# Power.net
KiCad netlist of a schematic drawn in Altium Designer
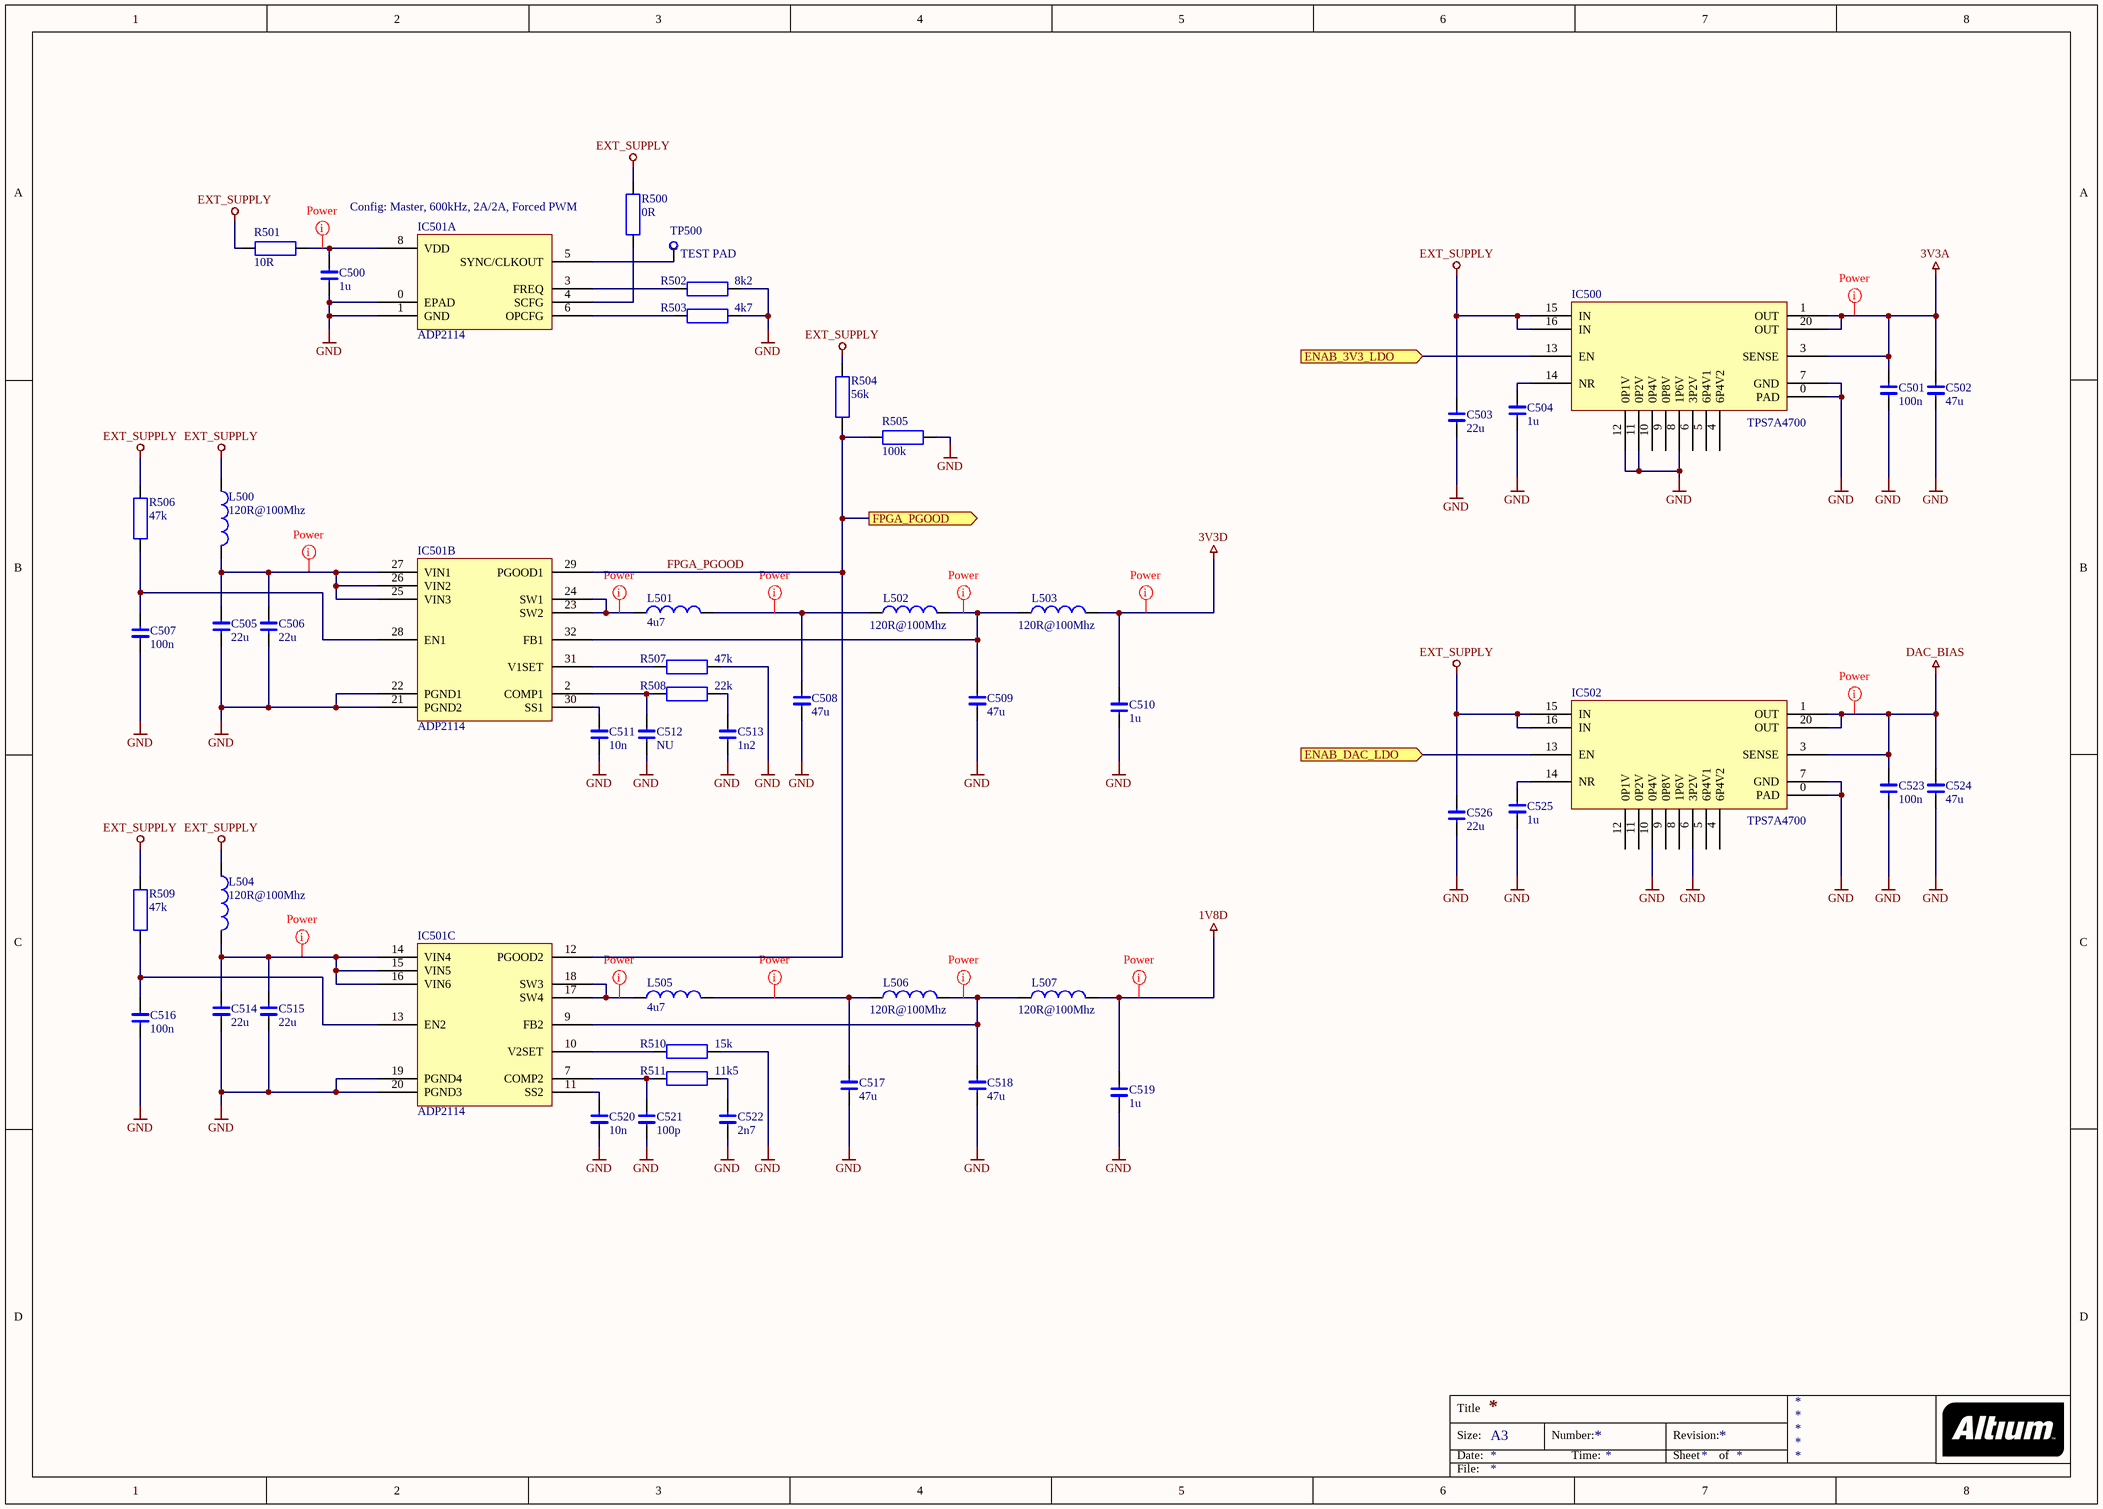
[diagram p0: Power.SchDoc]

(export (version "E")
  (design (tool "Eeschema 10.0.6"))
  (components
    (comp (ref "C500")
      (value "1u")
      (footprint "0603 SMALL OUTLINE")
      (description "C")
      (libsource (lib "RCL") (part "C"))
    )
    (comp (ref "C501")
      (value "100n")
      (footprint "0603 SMALL OUTLINE")
      (description "C")
      (libsource (lib "RCL") (part "C"))
    )
    (comp (ref "C502") (value "47u") (footprint "1206") (description "C") (libsource (lib "RCL") (part "C")))
    (comp (ref "C503") (value "22u") (footprint "1206") (description "C") (libsource (lib "RCL") (part "C")))
    (comp (ref "C504")
      (value "1u")
      (footprint "0603 SMALL OUTLINE")
      (description "C")
      (libsource (lib "RCL") (part "C"))
    )
    (comp (ref "C505") (value "22u") (footprint "1206") (description "C") (libsource (lib "RCL") (part "C")))
    (comp (ref "C506") (value "22u") (footprint "1206") (description "C") (libsource (lib "RCL") (part "C")))
    (comp (ref "C507")
      (value "100n")
      (footprint "0603 SMALL OUTLINE")
      (description "C")
      (libsource (lib "RCL") (part "C"))
    )
    (comp (ref "C508") (value "47u") (footprint "1206") (description "C") (libsource (lib "RCL") (part "C")))
    (comp (ref "C509") (value "47u") (footprint "1206") (description "C") (libsource (lib "RCL") (part "C")))
    (comp (ref "C510")
      (value "1u")
      (footprint "0603 SMALL OUTLINE")
      (description "C")
      (libsource (lib "RCL") (part "C"))
    )
    (comp (ref "C511")
      (value "10n")
      (footprint "0603 SMALL OUTLINE")
      (description "C")
      (libsource (lib "RCL") (part "C"))
    )
    (comp (ref "C512")
      (value "NU")
      (footprint "0603 SMALL OUTLINE")
      (description "C")
      (libsource (lib "RCL") (part "C"))
    )
    (comp (ref "C513")
      (value "1n2")
      (footprint "0603 SMALL OUTLINE")
      (description "C")
      (libsource (lib "RCL") (part "C"))
    )
    (comp (ref "C514") (value "22u") (footprint "1206") (description "C") (libsource (lib "RCL") (part "C")))
    (comp (ref "C515") (value "22u") (footprint "1206") (description "C") (libsource (lib "RCL") (part "C")))
    (comp (ref "C516")
      (value "100n")
      (footprint "0603 SMALL OUTLINE")
      (description "C")
      (libsource (lib "RCL") (part "C"))
    )
    (comp (ref "C517") (value "47u") (footprint "1206") (description "C") (libsource (lib "RCL") (part "C")))
    (comp (ref "C518") (value "47u") (footprint "1206") (description "C") (libsource (lib "RCL") (part "C")))
    (comp (ref "C519")
      (value "1u")
      (footprint "0603 SMALL OUTLINE")
      (description "C")
      (libsource (lib "RCL") (part "C"))
    )
    (comp (ref "C520")
      (value "10n")
      (footprint "0603 SMALL OUTLINE")
      (description "C")
      (libsource (lib "RCL") (part "C"))
    )
    (comp (ref "C521")
      (value "100p")
      (footprint "0603 SMALL OUTLINE")
      (description "C")
      (libsource (lib "RCL") (part "C"))
    )
    (comp (ref "C522")
      (value "2n7")
      (footprint "0603 SMALL OUTLINE")
      (description "C")
      (libsource (lib "RCL") (part "C"))
    )
    (comp (ref "C523")
      (value "100n")
      (footprint "0603 SMALL OUTLINE")
      (description "C")
      (libsource (lib "RCL") (part "C"))
    )
    (comp (ref "C524") (value "47u") (footprint "1206") (description "C") (libsource (lib "RCL") (part "C")))
    (comp (ref "C525")
      (value "1u")
      (footprint "0603 SMALL OUTLINE")
      (description "C")
      (libsource (lib "RCL") (part "C"))
    )
    (comp (ref "C526") (value "22u") (footprint "1206") (description "C") (libsource (lib "RCL") (part "C")))
    (comp (ref "IC500")
      (value "TPS7A4700")
      (footprint "VQFN20_LONG")
      (description "36V, 1A, Low Noise, RF LDO Voltage Regulator")
      (libsource (lib "REGLER1") (part "TPS7A4700"))
    )
    (comp (ref "IC501")
      (value "ADP2114")
      (footprint "LFCSP32_LONG")
      (description "Configurable DC/DC Sync. Buck, Dual 2A / Single 4A")
      (libsource (lib "REGLER1") (part "ADP2114"))
    )
    (comp (ref "IC502")
      (value "TPS7A4700")
      (footprint "VQFN20_LONG")
      (description "36V, 1A, Low Noise, RF LDO Voltage Regulator")
      (libsource (lib "REGLER1") (part "TPS7A4700"))
    )
    (comp (ref "L500")
      (value "120R@100Mhz")
      (footprint "0805")
      (description "742792023")
      (libsource (lib "RCL") (part "L"))
    )
    (comp (ref "L501")
      (value "4u7")
      (footprint "DR74")
      (description "DR74-XXX-R")
      (libsource (lib "RCL") (part "L"))
    )
    (comp (ref "L502")
      (value "120R@100Mhz")
      (footprint "0805")
      (description "742792023")
      (libsource (lib "RCL") (part "L"))
    )
    (comp (ref "L503")
      (value "120R@100Mhz")
      (footprint "0805")
      (description "742792023")
      (libsource (lib "RCL") (part "L"))
    )
    (comp (ref "L504")
      (value "120R@100Mhz")
      (footprint "0805")
      (description "742792023")
      (libsource (lib "RCL") (part "L"))
    )
    (comp (ref "L505")
      (value "4u7")
      (footprint "DR74")
      (description "DR74-XXX-R")
      (libsource (lib "RCL") (part "L"))
    )
    (comp (ref "L506")
      (value "120R@100Mhz")
      (footprint "0805")
      (description "742792023")
      (libsource (lib "RCL") (part "L"))
    )
    (comp (ref "L507")
      (value "120R@100Mhz")
      (footprint "0805")
      (description "742792023")
      (libsource (lib "RCL") (part "L"))
    )
    (comp (ref "R500")
      (value "0R")
      (footprint "0603 SMALL OUTLINE")
      (description "R")
      (libsource (lib "RCL") (part "R"))
    )
    (comp (ref "R501")
      (value "10R")
      (footprint "0603 SMALL OUTLINE")
      (description "R")
      (libsource (lib "RCL") (part "R"))
    )
    (comp (ref "R502")
      (value "8k2")
      (footprint "0603 SMALL OUTLINE")
      (description "R")
      (libsource (lib "RCL") (part "R"))
    )
    (comp (ref "R503")
      (value "4k7")
      (footprint "0603 SMALL OUTLINE")
      (description "R")
      (libsource (lib "RCL") (part "R"))
    )
    (comp (ref "R504")
      (value "56k")
      (footprint "0603 SMALL OUTLINE")
      (description "R")
      (libsource (lib "RCL") (part "R"))
    )
    (comp (ref "R505")
      (value "100k")
      (footprint "0603 SMALL OUTLINE")
      (description "R")
      (libsource (lib "RCL") (part "R"))
    )
    (comp (ref "R506")
      (value "47k")
      (footprint "0603 SMALL OUTLINE")
      (description "R")
      (libsource (lib "RCL") (part "R"))
    )
    (comp (ref "R507")
      (value "47k")
      (footprint "0603 SMALL OUTLINE")
      (description "R")
      (libsource (lib "RCL") (part "R"))
    )
    (comp (ref "R508")
      (value "22k")
      (footprint "0603 SMALL OUTLINE")
      (description "R")
      (libsource (lib "RCL") (part "R"))
    )
    (comp (ref "R509")
      (value "47k")
      (footprint "0603 SMALL OUTLINE")
      (description "R")
      (libsource (lib "RCL") (part "R"))
    )
    (comp (ref "R510")
      (value "15k")
      (footprint "0603 SMALL OUTLINE")
      (description "R")
      (libsource (lib "RCL") (part "R"))
    )
    (comp (ref "R511")
      (value "11k5")
      (footprint "0603 SMALL OUTLINE")
      (description "R")
      (libsource (lib "RCL") (part "R"))
    )
    (comp (ref "TP500")
      (value "TEST PAD")
      (footprint "TEST_PAD_50")
      (description "Test Pad")
      (libsource (lib "SPECIAL1") (part "TEST PAD"))
    )
  )
  (nets
    (net (code "1") (name "/ENAB_3V3_LDO") (class "Default")
      (node (ref "IC500") (pin "13") (pinfunction "EN_13") (pintype "passive"))
    )
    (net (code "2") (name "/ENAB_DAC_LDO") (class "Default")
      (node (ref "IC502") (pin "13") (pinfunction "EN_13") (pintype "passive"))
    )
    (net (code "3") (name "/FPGA_PGOOD") (class "Default")
      (node (ref "IC501") (pin "12") (pinfunction "PGOOD2_12") (pintype "passive"))
      (node (ref "IC501") (pin "29") (pinfunction "PGOOD1_29") (pintype "passive"))
      (node (ref "R504") (pin "2") (pinfunction "2_2") (pintype "passive"))
      (node (ref "R505") (pin "1") (pinfunction "1_1") (pintype "passive"))
    )
    (net (code "4") (name "1V8D") (class "Default")
      (node (ref "C519") (pin "1") (pinfunction "1_1") (pintype "passive"))
      (node (ref "L507") (pin "2") (pinfunction "2_2") (pintype "passive"))
    )
    (net (code "5") (name "3V3A") (class "Default")
      (node (ref "C501") (pin "1") (pinfunction "1_1") (pintype "passive"))
      (node (ref "C502") (pin "1") (pinfunction "1_1") (pintype "passive"))
      (node (ref "IC500") (pin "1") (pinfunction "OUT_1") (pintype "passive"))
      (node (ref "IC500") (pin "20") (pinfunction "OUT_20") (pintype "passive"))
      (node (ref "IC500") (pin "3") (pinfunction "SENSE_3") (pintype "passive"))
    )
    (net (code "6") (name "3V3D") (class "Default")
      (node (ref "C510") (pin "1") (pinfunction "1_1") (pintype "passive"))
      (node (ref "L503") (pin "2") (pinfunction "2_2") (pintype "passive"))
    )
    (net (code "7") (name "DAC_BIAS") (class "Default")
      (node (ref "C523") (pin "1") (pinfunction "1_1") (pintype "passive"))
      (node (ref "C524") (pin "1") (pinfunction "1_1") (pintype "passive"))
      (node (ref "IC502") (pin "1") (pinfunction "OUT_1") (pintype "passive"))
      (node (ref "IC502") (pin "20") (pinfunction "OUT_20") (pintype "passive"))
      (node (ref "IC502") (pin "3") (pinfunction "SENSE_3") (pintype "passive"))
    )
    (net (code "8") (name "EXT_SUPPLY") (class "Default")
      (node (ref "C503") (pin "1") (pinfunction "1_1") (pintype "passive"))
      (node (ref "C526") (pin "1") (pinfunction "1_1") (pintype "passive"))
      (node (ref "IC500") (pin "15") (pinfunction "IN_15") (pintype "passive"))
      (node (ref "IC500") (pin "16") (pinfunction "IN_16") (pintype "passive"))
      (node (ref "IC502") (pin "15") (pinfunction "IN_15") (pintype "passive"))
      (node (ref "IC502") (pin "16") (pinfunction "IN_16") (pintype "passive"))
      (node (ref "L500") (pin "1") (pinfunction "1_1") (pintype "passive"))
      (node (ref "L504") (pin "1") (pinfunction "1_1") (pintype "passive"))
      (node (ref "R500") (pin "1") (pinfunction "1_1") (pintype "passive"))
      (node (ref "R501") (pin "2") (pinfunction "2_2") (pintype "passive"))
      (node (ref "R504") (pin "1") (pinfunction "1_1") (pintype "passive"))
      (node (ref "R506") (pin "2") (pinfunction "2_2") (pintype "passive"))
      (node (ref "R509") (pin "2") (pinfunction "2_2") (pintype "passive"))
    )
    (net (code "9") (name "GND") (class "Default")
      (node (ref "C500") (pin "1") (pinfunction "1_1") (pintype "passive"))
      (node (ref "C501") (pin "2") (pinfunction "2_2") (pintype "passive"))
      (node (ref "C502") (pin "2") (pinfunction "2_2") (pintype "passive"))
      (node (ref "C503") (pin "2") (pinfunction "2_2") (pintype "passive"))
      (node (ref "C504") (pin "1") (pinfunction "1_1") (pintype "passive"))
      (node (ref "C505") (pin "2") (pinfunction "2_2") (pintype "passive"))
      (node (ref "C506") (pin "2") (pinfunction "2_2") (pintype "passive"))
      (node (ref "C507") (pin "2") (pinfunction "2_2") (pintype "passive"))
      (node (ref "C508") (pin "2") (pinfunction "2_2") (pintype "passive"))
      (node (ref "C509") (pin "2") (pinfunction "2_2") (pintype "passive"))
      (node (ref "C510") (pin "2") (pinfunction "2_2") (pintype "passive"))
      (node (ref "C511") (pin "2") (pinfunction "2_2") (pintype "passive"))
      (node (ref "C512") (pin "2") (pinfunction "2_2") (pintype "passive"))
      (node (ref "C513") (pin "2") (pinfunction "2_2") (pintype "passive"))
      (node (ref "C514") (pin "2") (pinfunction "2_2") (pintype "passive"))
      (node (ref "C515") (pin "2") (pinfunction "2_2") (pintype "passive"))
      (node (ref "C516") (pin "2") (pinfunction "2_2") (pintype "passive"))
      (node (ref "C517") (pin "2") (pinfunction "2_2") (pintype "passive"))
      (node (ref "C518") (pin "2") (pinfunction "2_2") (pintype "passive"))
      (node (ref "C519") (pin "2") (pinfunction "2_2") (pintype "passive"))
      (node (ref "C520") (pin "2") (pinfunction "2_2") (pintype "passive"))
      (node (ref "C521") (pin "2") (pinfunction "2_2") (pintype "passive"))
      (node (ref "C522") (pin "2") (pinfunction "2_2") (pintype "passive"))
      (node (ref "C523") (pin "2") (pinfunction "2_2") (pintype "passive"))
      (node (ref "C524") (pin "2") (pinfunction "2_2") (pintype "passive"))
      (node (ref "C525") (pin "1") (pinfunction "1_1") (pintype "passive"))
      (node (ref "C526") (pin "2") (pinfunction "2_2") (pintype "passive"))
      (node (ref "IC500") (pin "0") (pinfunction "PAD_0") (pintype "passive"))
      (node (ref "IC500") (pin "11") (pinfunction "0P2V_11") (pintype "passive"))
      (node (ref "IC500") (pin "12") (pinfunction "0P1V_12") (pintype "passive"))
      (node (ref "IC500") (pin "7") (pinfunction "GND_7") (pintype "passive"))
      (node (ref "IC500") (pin "8") (pinfunction "1P6V_8") (pintype "passive"))
      (node (ref "IC501") (pin "0") (pinfunction "EPAD_0") (pintype "passive"))
      (node (ref "IC501") (pin "1") (pinfunction "GND_1") (pintype "passive"))
      (node (ref "IC501") (pin "19") (pinfunction "PGND4_19") (pintype "passive"))
      (node (ref "IC501") (pin "20") (pinfunction "PGND3_20") (pintype "passive"))
      (node (ref "IC501") (pin "21") (pinfunction "PGND2_21") (pintype "passive"))
      (node (ref "IC501") (pin "22") (pinfunction "PGND1_22") (pintype "passive"))
      (node (ref "IC502") (pin "0") (pinfunction "PAD_0") (pintype "passive"))
      (node (ref "IC502") (pin "10") (pinfunction "0P4V_10") (pintype "passive"))
      (node (ref "IC502") (pin "6") (pinfunction "3P2V_6") (pintype "passive"))
      (node (ref "IC502") (pin "7") (pinfunction "GND_7") (pintype "passive"))
      (node (ref "R502") (pin "2") (pinfunction "2_2") (pintype "passive"))
      (node (ref "R503") (pin "2") (pinfunction "2_2") (pintype "passive"))
      (node (ref "R505") (pin "2") (pinfunction "2_2") (pintype "passive"))
      (node (ref "R507") (pin "2") (pinfunction "2_2") (pintype "passive"))
      (node (ref "R510") (pin "2") (pinfunction "2_2") (pintype "passive"))
    )
    (net (code "10") (name "Net-(C508-Pad1)") (class "Default")
      (node (ref "C508") (pin "1") (pinfunction "1_1") (pintype "passive"))
      (node (ref "L501") (pin "2") (pinfunction "2_2") (pintype "passive"))
      (node (ref "L502") (pin "1") (pinfunction "1_1") (pintype "passive"))
    )
    (net (code "11") (name "Net-(C513-Pad1)") (class "Default")
      (node (ref "C513") (pin "1") (pinfunction "1_1") (pintype "passive"))
      (node (ref "R508") (pin "2") (pinfunction "2_2") (pintype "passive"))
    )
    (net (code "12") (name "Net-(C517-Pad1)") (class "Default")
      (node (ref "C517") (pin "1") (pinfunction "1_1") (pintype "passive"))
      (node (ref "L505") (pin "2") (pinfunction "2_2") (pintype "passive"))
      (node (ref "L506") (pin "1") (pinfunction "1_1") (pintype "passive"))
    )
    (net (code "13") (name "Net-(C522-Pad1)") (class "Default")
      (node (ref "C522") (pin "1") (pinfunction "1_1") (pintype "passive"))
      (node (ref "R511") (pin "2") (pinfunction "2_2") (pintype "passive"))
    )
    (net (code "14") (name "Net-(IC500-NR)") (class "Default")
      (node (ref "C504") (pin "2") (pinfunction "2_2") (pintype "passive"))
      (node (ref "IC500") (pin "14") (pinfunction "NR_14") (pintype "passive"))
    )
    (net (code "15") (name "Net-(IC501A-FREQ)") (class "Default")
      (node (ref "IC501") (pin "3") (pinfunction "FREQ_3") (pintype "passive"))
      (node (ref "R502") (pin "1") (pinfunction "1_1") (pintype "passive"))
    )
    (net (code "16") (name "Net-(IC501A-OPCFG)") (class "Default")
      (node (ref "IC501") (pin "6") (pinfunction "OPCFG_6") (pintype "passive"))
      (node (ref "R503") (pin "1") (pinfunction "1_1") (pintype "passive"))
    )
    (net (code "17") (name "Net-(IC501A-SCFG)") (class "Default")
      (node (ref "IC501") (pin "4") (pinfunction "SCFG_4") (pintype "passive"))
      (node (ref "R500") (pin "2") (pinfunction "2_2") (pintype "passive"))
    )
    (net (code "18") (name "Net-(IC501A-SYNC{slash}CLKOUT)") (class "Default")
      (node (ref "IC501") (pin "5") (pinfunction "SYNC/CLKOUT_5") (pintype "passive"))
      (node (ref "TP500") (pin "0") (pinfunction "0_0") (pintype "passive"))
    )
    (net (code "19") (name "Net-(IC501A-VDD)") (class "Default")
      (node (ref "C500") (pin "2") (pinfunction "2_2") (pintype "passive"))
      (node (ref "IC501") (pin "8") (pinfunction "VDD_8") (pintype "passive"))
      (node (ref "R501") (pin "1") (pinfunction "1_1") (pintype "passive"))
    )
    (net (code "20") (name "Net-(IC501B-COMP1)") (class "Default")
      (node (ref "C512") (pin "1") (pinfunction "1_1") (pintype "passive"))
      (node (ref "IC501") (pin "2") (pinfunction "COMP1_2") (pintype "passive"))
      (node (ref "R508") (pin "1") (pinfunction "1_1") (pintype "passive"))
    )
    (net (code "21") (name "Net-(IC501B-EN1)") (class "Default")
      (node (ref "C507") (pin "1") (pinfunction "1_1") (pintype "passive"))
      (node (ref "IC501") (pin "28") (pinfunction "EN1_28") (pintype "passive"))
      (node (ref "R506") (pin "1") (pinfunction "1_1") (pintype "passive"))
    )
    (net (code "22") (name "Net-(IC501B-FB1)") (class "Default")
      (node (ref "C509") (pin "1") (pinfunction "1_1") (pintype "passive"))
      (node (ref "IC501") (pin "32") (pinfunction "FB1_32") (pintype "passive"))
      (node (ref "L502") (pin "2") (pinfunction "2_2") (pintype "passive"))
      (node (ref "L503") (pin "1") (pinfunction "1_1") (pintype "passive"))
    )
    (net (code "23") (name "Net-(IC501B-SS1)") (class "Default")
      (node (ref "C511") (pin "1") (pinfunction "1_1") (pintype "passive"))
      (node (ref "IC501") (pin "30") (pinfunction "SS1_30") (pintype "passive"))
    )
    (net (code "24") (name "Net-(IC501B-SW1)") (class "Default")
      (node (ref "IC501") (pin "23") (pinfunction "SW2_23") (pintype "passive"))
      (node (ref "IC501") (pin "24") (pinfunction "SW1_24") (pintype "passive"))
      (node (ref "L501") (pin "1") (pinfunction "1_1") (pintype "passive"))
    )
    (net (code "25") (name "Net-(IC501B-V1SET)") (class "Default")
      (node (ref "IC501") (pin "31") (pinfunction "V1SET_31") (pintype "passive"))
      (node (ref "R507") (pin "1") (pinfunction "1_1") (pintype "passive"))
    )
    (net (code "26") (name "Net-(IC501B-VIN1)") (class "Default")
      (node (ref "C505") (pin "1") (pinfunction "1_1") (pintype "passive"))
      (node (ref "C506") (pin "1") (pinfunction "1_1") (pintype "passive"))
      (node (ref "IC501") (pin "25") (pinfunction "VIN3_25") (pintype "passive"))
      (node (ref "IC501") (pin "26") (pinfunction "VIN2_26") (pintype "passive"))
      (node (ref "IC501") (pin "27") (pinfunction "VIN1_27") (pintype "passive"))
      (node (ref "L500") (pin "2") (pinfunction "2_2") (pintype "passive"))
    )
    (net (code "27") (name "Net-(IC501C-COMP2)") (class "Default")
      (node (ref "C521") (pin "1") (pinfunction "1_1") (pintype "passive"))
      (node (ref "IC501") (pin "7") (pinfunction "COMP2_7") (pintype "passive"))
      (node (ref "R511") (pin "1") (pinfunction "1_1") (pintype "passive"))
    )
    (net (code "28") (name "Net-(IC501C-EN2)") (class "Default")
      (node (ref "C516") (pin "1") (pinfunction "1_1") (pintype "passive"))
      (node (ref "IC501") (pin "13") (pinfunction "EN2_13") (pintype "passive"))
      (node (ref "R509") (pin "1") (pinfunction "1_1") (pintype "passive"))
    )
    (net (code "29") (name "Net-(IC501C-FB2)") (class "Default")
      (node (ref "C518") (pin "1") (pinfunction "1_1") (pintype "passive"))
      (node (ref "IC501") (pin "9") (pinfunction "FB2_9") (pintype "passive"))
      (node (ref "L506") (pin "2") (pinfunction "2_2") (pintype "passive"))
      (node (ref "L507") (pin "1") (pinfunction "1_1") (pintype "passive"))
    )
    (net (code "30") (name "Net-(IC501C-SS2)") (class "Default")
      (node (ref "C520") (pin "1") (pinfunction "1_1") (pintype "passive"))
      (node (ref "IC501") (pin "11") (pinfunction "SS2_11") (pintype "passive"))
    )
    (net (code "31") (name "Net-(IC501C-SW3)") (class "Default")
      (node (ref "IC501") (pin "17") (pinfunction "SW4_17") (pintype "passive"))
      (node (ref "IC501") (pin "18") (pinfunction "SW3_18") (pintype "passive"))
      (node (ref "L505") (pin "1") (pinfunction "1_1") (pintype "passive"))
    )
    (net (code "32") (name "Net-(IC501C-V2SET)") (class "Default")
      (node (ref "IC501") (pin "10") (pinfunction "V2SET_10") (pintype "passive"))
      (node (ref "R510") (pin "1") (pinfunction "1_1") (pintype "passive"))
    )
    (net (code "33") (name "Net-(IC501C-VIN4)") (class "Default")
      (node (ref "C514") (pin "1") (pinfunction "1_1") (pintype "passive"))
      (node (ref "C515") (pin "1") (pinfunction "1_1") (pintype "passive"))
      (node (ref "IC501") (pin "14") (pinfunction "VIN4_14") (pintype "passive"))
      (node (ref "IC501") (pin "15") (pinfunction "VIN5_15") (pintype "passive"))
      (node (ref "IC501") (pin "16") (pinfunction "VIN6_16") (pintype "passive"))
      (node (ref "L504") (pin "2") (pinfunction "2_2") (pintype "passive"))
    )
    (net (code "34") (name "Net-(IC502-NR)") (class "Default")
      (node (ref "C525") (pin "2") (pinfunction "2_2") (pintype "passive"))
      (node (ref "IC502") (pin "14") (pinfunction "NR_14") (pintype "passive"))
    )
    (net (code "35") (name "unconnected-(IC500-0P4V-Pad10)") (class "Default")
      (node (ref "IC500") (pin "10") (pinfunction "0P4V_10") (pintype "passive"))
    )
    (net (code "36") (name "unconnected-(IC500-0P8V-Pad9)") (class "Default")
      (node (ref "IC500") (pin "9") (pinfunction "0P8V_9") (pintype "passive"))
    )
    (net (code "37") (name "unconnected-(IC500-3P2V-Pad6)") (class "Default")
      (node (ref "IC500") (pin "6") (pinfunction "3P2V_6") (pintype "passive"))
    )
    (net (code "38") (name "unconnected-(IC500-6P4V1-Pad5)") (class "Default")
      (node (ref "IC500") (pin "5") (pinfunction "6P4V1_5") (pintype "passive"))
    )
    (net (code "39") (name "unconnected-(IC500-6P4V2-Pad4)") (class "Default")
      (node (ref "IC500") (pin "4") (pinfunction "6P4V2_4") (pintype "passive"))
    )
    (net (code "40") (name "unconnected-(IC502-0P1V-Pad12)") (class "Default")
      (node (ref "IC502") (pin "12") (pinfunction "0P1V_12") (pintype "passive"))
    )
    (net (code "41") (name "unconnected-(IC502-0P2V-Pad11)") (class "Default")
      (node (ref "IC502") (pin "11") (pinfunction "0P2V_11") (pintype "passive"))
    )
    (net (code "42") (name "unconnected-(IC502-0P8V-Pad9)") (class "Default")
      (node (ref "IC502") (pin "9") (pinfunction "0P8V_9") (pintype "passive"))
    )
    (net (code "43") (name "unconnected-(IC502-1P6V-Pad8)") (class "Default")
      (node (ref "IC502") (pin "8") (pinfunction "1P6V_8") (pintype "passive"))
    )
    (net (code "44") (name "unconnected-(IC502-6P4V1-Pad5)") (class "Default")
      (node (ref "IC502") (pin "5") (pinfunction "6P4V1_5") (pintype "passive"))
    )
    (net (code "45") (name "unconnected-(IC502-6P4V2-Pad4)") (class "Default")
      (node (ref "IC502") (pin "4") (pinfunction "6P4V2_4") (pintype "passive"))
    )
  )
)
